# BC7.net
KiCad netlist of a schematic drawn in EAGLE
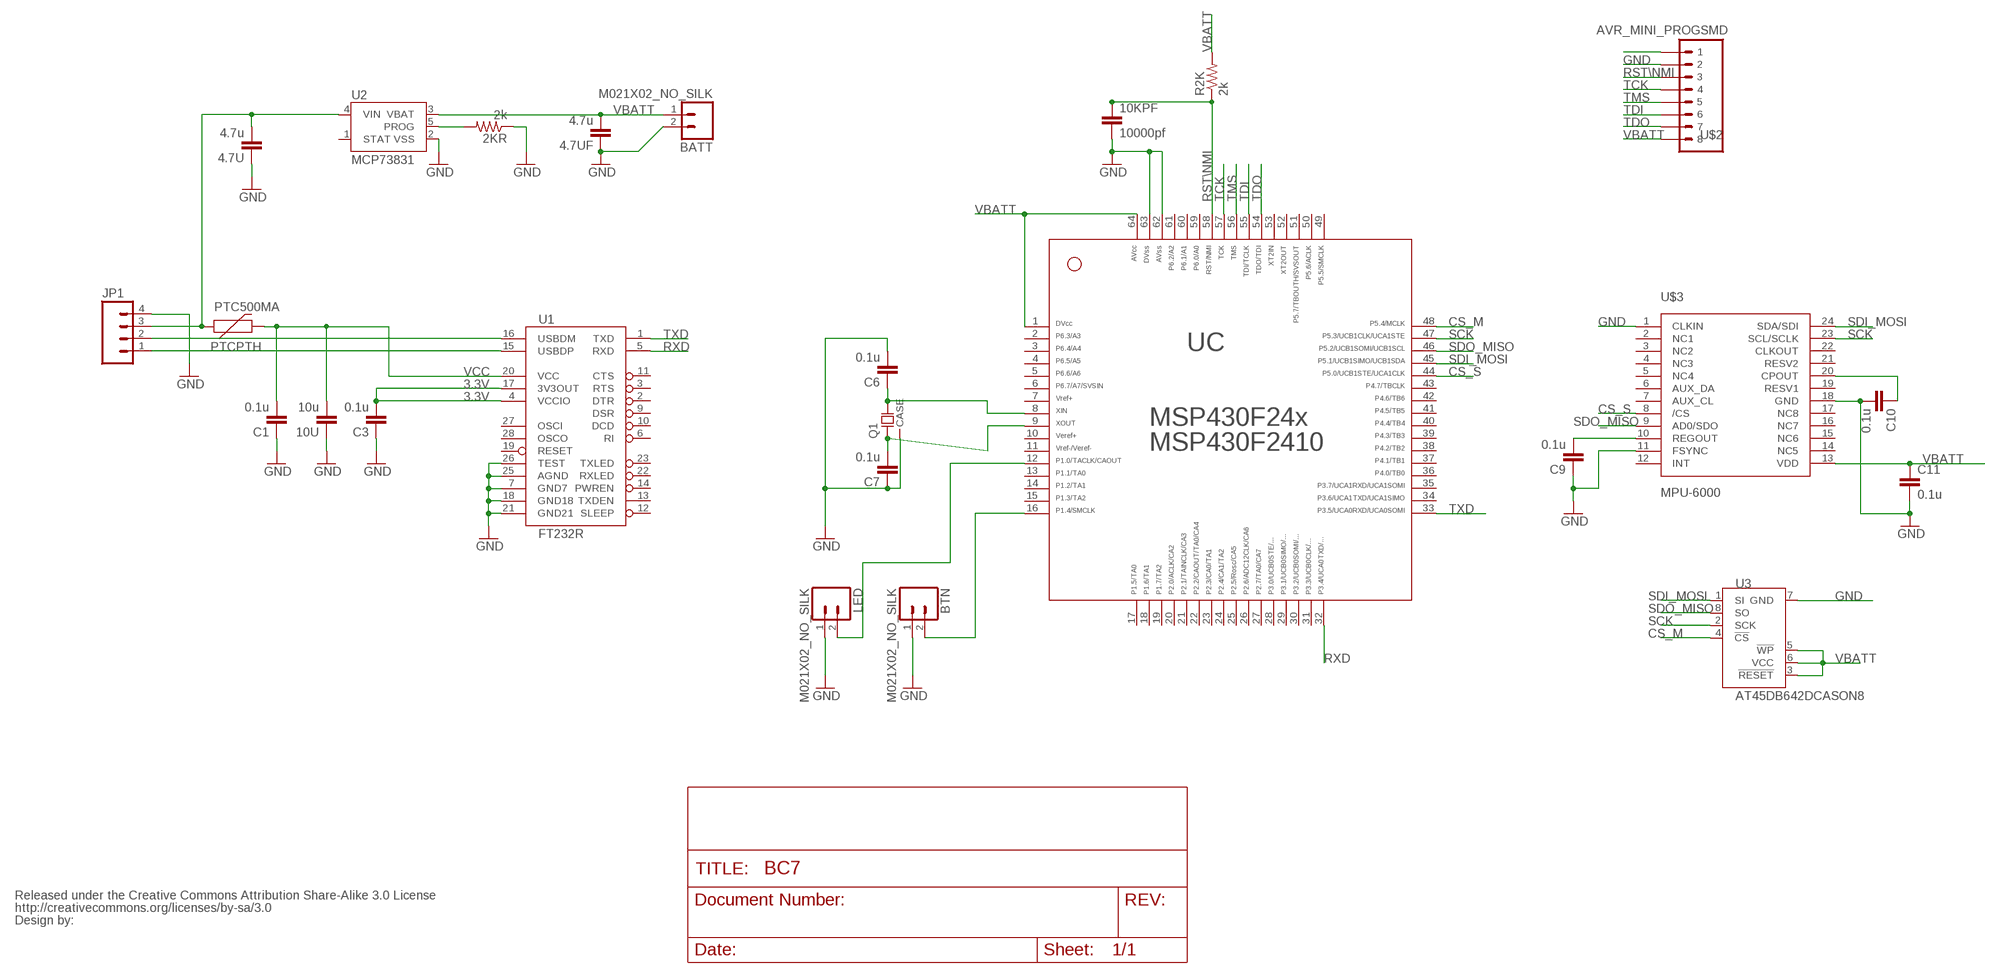
[diagram p0: schematic, sheet 1]

(export (version "E")
  (design (tool "Eeschema 10.0.6"))
  (components
    (comp (ref "2KR")
      (value "2k")
      (footprint "eagle-import:0402-RES")
      (libsource (lib "eagle-import") (part "RESISTOR0402-RES"))
    )
    (comp (ref "4.7U")
      (value "4.7u")
      (footprint "eagle-import:0402-CAP")
      (libsource (lib "eagle-import") (part "CAP0402-CAP"))
    )
    (comp (ref "4.7UF")
      (value "4.7u")
      (footprint "eagle-import:0402-CAP")
      (libsource (lib "eagle-import") (part "CAP0402-CAP"))
    )
    (comp (ref "10KPF")
      (value "10000pf")
      (footprint "eagle-import:CAP-PTH-SMALLEZ")
      (libsource (lib "eagle-import") (part "SparkFun-Passives_CAPEZ"))
    )
    (comp (ref "10U")
      (value "10u")
      (footprint "eagle-import:0402-CAP")
      (libsource (lib "eagle-import") (part "CAP0402-CAP"))
    )
    (comp (ref "BATT")
      (value "M021X02_NO_SILK")
      (footprint "eagle-import:1X02_NO_SILK")
      (libsource (lib "eagle-import") (part "M021X02_NO_SILK"))
    )
    (comp (ref "BTN")
      (value "M021X02_NO_SILK")
      (footprint "eagle-import:1X02_NO_SILK")
      (libsource (lib "eagle-import") (part "M021X02_NO_SILK"))
    )
    (comp (ref "C1")
      (value "0.1u")
      (footprint "eagle-import:0402-CAP")
      (libsource (lib "eagle-import") (part "CAP0402-CAP"))
    )
    (comp (ref "C3")
      (value "0.1u")
      (footprint "eagle-import:0402-CAP")
      (libsource (lib "eagle-import") (part "CAP0402-CAP"))
    )
    (comp (ref "C6")
      (value "0.1u")
      (footprint "eagle-import:0402-CAP")
      (libsource (lib "eagle-import") (part "CAP0402-CAP"))
    )
    (comp (ref "C7")
      (value "0.1u")
      (footprint "eagle-import:0402-CAP")
      (libsource (lib "eagle-import") (part "CAP0402-CAP"))
    )
    (comp (ref "C9")
      (value "0.1u")
      (footprint "eagle-import:0402-CAP")
      (libsource (lib "eagle-import") (part "CAP0402-CAP"))
    )
    (comp (ref "C10")
      (value "0.1u")
      (footprint "eagle-import:0402-CAP")
      (libsource (lib "eagle-import") (part "CAP0402-CAP"))
    )
    (comp (ref "C11")
      (value "0.1u")
      (footprint "eagle-import:0402-CAP")
      (libsource (lib "eagle-import") (part "CAP0402-CAP"))
    )
    (comp (ref "JP1")
      (value "M04LOCK")
      (footprint "eagle-import:1X04_LOCK")
      (libsource (lib "eagle-import") (part "M04LOCK"))
    )
    (comp (ref "LED")
      (value "M021X02_NO_SILK")
      (footprint "eagle-import:1X02_NO_SILK")
      (libsource (lib "eagle-import") (part "M021X02_NO_SILK"))
    )
    (comp (ref "PTC500MA")
      (value "PTCPTH")
      (footprint "eagle-import:PTC")
      (libsource (lib "eagle-import") (part "PTCPTH"))
    )
    (comp (ref "Q1")
      (value "MS1V-T1K-32.768KHZ/12.5PF/20PPM/TA/QC")
      (footprint "eagle-import:MS1V-T1K")
      (libsource (lib "eagle-import") (part "MS1V-T1K-32.768KHZ/12.5PF/20PPM/TA/QC"))
    )
    (comp (ref "R2K")
      (value "2k")
      (footprint "eagle-import:0204_5")
      (libsource (lib "eagle-import") (part "R-US_0204/5"))
    )
    (comp (ref "U$1")
      (value "CREATIVE_COMMONS")
      (footprint "eagle-import:CREATIVE_COMMONS")
      (libsource (lib "eagle-import") (part "CREATIVE_COMMONS"))
    )
    (comp (ref "U$2")
      (value "AVR_MINI_PROGSMD")
      (footprint "eagle-import:AVR_MINI_PROG")
      (libsource (lib "eagle-import") (part "AVR_MINI_PROGSMD"))
    )
    (comp (ref "U$3")
      (value "MPU-6000")
      (footprint "eagle-import:QFN-24")
      (libsource (lib "eagle-import") (part "MPU-6000"))
    )
    (comp (ref "U1")
      (value "FT232R")
      (footprint "eagle-import:SSOP28DB")
      (libsource (lib "eagle-import") (part "FT232RLSSOP"))
    )
    (comp (ref "U2")
      (value "MCP73831")
      (footprint "eagle-import:SOT23-5")
      (libsource (lib "eagle-import") (part "MCP73831"))
    )
    (comp (ref "U3")
      (value "AT45DB642DCASON8")
      (footprint "eagle-import:CASON8")
      (libsource (lib "eagle-import") (part "AT45DB642DCASON8"))
    )
    (comp (ref "UC")
      (value "F24[X/10]---PM64")
      (footprint "eagle-import:PM_PAG64")
      (libsource (lib "eagle-import") (part "F24[X/10]---PM64"))
    )
  )
  (nets
    (net (code "1") (name "/3.3V") (class "Default")
      (node (ref "C3") (pin "2") (pinfunction "2_2") (pintype "passive"))
      (node (ref "U1") (pin "17") (pinfunction "3V3OUT_17") (pintype "output"))
      (node (ref "U1") (pin "4") (pinfunction "VCCIO_4") (pintype "power_in"))
    )
    (net (code "2") (name "/CS_M") (class "Default")
      (node (ref "U3") (pin "4") (pinfunction "~{CS}_4") (pintype "input"))
      (node (ref "UC") (pin "48") (pinfunction "48_48") (pintype "bidirectional"))
    )
    (net (code "3") (name "/CS_S") (class "Default")
      (node (ref "U$3") (pin "8") (pinfunction "/CS_8") (pintype "bidirectional"))
      (node (ref "UC") (pin "44") (pinfunction "44_44") (pintype "bidirectional"))
    )
    (net (code "4") (name "/RST\\NMI") (class "Default")
      (node (ref "10KPF") (pin "1") (pinfunction "1_1") (pintype "passive"))
      (node (ref "R2K") (pin "1") (pinfunction "1_1") (pintype "passive"))
      (node (ref "U$2") (pin "3") (pinfunction "3_3") (pintype "passive"))
      (node (ref "UC") (pin "58") (pinfunction "58_58") (pintype "input"))
    )
    (net (code "5") (name "/RXD") (class "Default")
      (node (ref "U1") (pin "5") (pinfunction "RXD_5") (pintype "input"))
      (node (ref "UC") (pin "32") (pinfunction "32_32") (pintype "bidirectional"))
    )
    (net (code "6") (name "/SCK") (class "Default")
      (node (ref "U$3") (pin "23") (pinfunction "SCL/SCLK_23") (pintype "bidirectional"))
      (node (ref "U3") (pin "2") (pinfunction "SCK_2") (pintype "input"))
      (node (ref "UC") (pin "47") (pinfunction "47_47") (pintype "bidirectional"))
    )
    (net (code "7") (name "/SDI_MOSI") (class "Default")
      (node (ref "U$3") (pin "24") (pinfunction "SDA/SDI_24") (pintype "bidirectional"))
      (node (ref "U3") (pin "1") (pinfunction "SI_1") (pintype "input"))
      (node (ref "UC") (pin "45") (pinfunction "45_45") (pintype "bidirectional"))
    )
    (net (code "8") (name "/SDO_MISO") (class "Default")
      (node (ref "U$3") (pin "9") (pinfunction "AD0/SDO_9") (pintype "bidirectional"))
      (node (ref "U3") (pin "8") (pinfunction "SO_8") (pintype "output"))
      (node (ref "UC") (pin "46") (pinfunction "46_46") (pintype "bidirectional"))
    )
    (net (code "9") (name "/TCK") (class "Default")
      (node (ref "U$2") (pin "4") (pinfunction "4_4") (pintype "passive"))
      (node (ref "UC") (pin "57") (pinfunction "57_57") (pintype "input"))
    )
    (net (code "10") (name "/TDI") (class "Default")
      (node (ref "U$2") (pin "6") (pinfunction "6_6") (pintype "passive"))
      (node (ref "UC") (pin "55") (pinfunction "55_55") (pintype "input"))
    )
    (net (code "11") (name "/TDO") (class "Default")
      (node (ref "U$2") (pin "7") (pinfunction "7_7") (pintype "passive"))
      (node (ref "UC") (pin "54") (pinfunction "54_54") (pintype "bidirectional"))
    )
    (net (code "12") (name "/TMS") (class "Default")
      (node (ref "U$2") (pin "5") (pinfunction "5_5") (pintype "passive"))
      (node (ref "UC") (pin "56") (pinfunction "56_56") (pintype "input"))
    )
    (net (code "13") (name "/TXD") (class "Default")
      (node (ref "U1") (pin "1") (pinfunction "TXD_1") (pintype "output"))
      (node (ref "UC") (pin "33") (pinfunction "33_33") (pintype "bidirectional"))
    )
    (net (code "14") (name "/VBATT") (class "Default")
      (node (ref "4.7UF") (pin "2") (pinfunction "2_2") (pintype "passive"))
      (node (ref "BATT") (pin "1") (pinfunction "1_1") (pintype "passive"))
      (node (ref "C11") (pin "1") (pinfunction "1_1") (pintype "passive"))
      (node (ref "R2K") (pin "2") (pinfunction "2_2") (pintype "passive"))
      (node (ref "U$2") (pin "8") (pinfunction "8_8") (pintype "passive"))
      (node (ref "U$3") (pin "13") (pinfunction "VDD_13") (pintype "bidirectional"))
      (node (ref "U2") (pin "3") (pinfunction "VBAT_3") (pintype "power_in"))
      (node (ref "U3") (pin "3") (pinfunction "~{RESET}_3") (pintype "input"))
      (node (ref "U3") (pin "5") (pinfunction "~{WP}_5") (pintype "input"))
      (node (ref "U3") (pin "6") (pinfunction "VCC_6") (pintype "power_in"))
      (node (ref "UC") (pin "1") (pinfunction "1_1") (pintype "power_in"))
      (node (ref "UC") (pin "64") (pinfunction "64_64") (pintype "power_in"))
    )
    (net (code "15") (name "/VCC") (class "Default")
      (node (ref "10U") (pin "2") (pinfunction "2_2") (pintype "passive"))
      (node (ref "C1") (pin "2") (pinfunction "2_2") (pintype "passive"))
      (node (ref "PTC500MA") (pin "P$2") (pinfunction "2_P$2") (pintype "bidirectional"))
      (node (ref "U1") (pin "20") (pinfunction "VCC_20") (pintype "power_in"))
    )
    (net (code "16") (name "GND") (class "Default")
      (node (ref "10KPF") (pin "2") (pinfunction "2_2") (pintype "passive"))
      (node (ref "10U") (pin "1") (pinfunction "1_1") (pintype "passive"))
      (node (ref "2KR") (pin "1") (pinfunction "1_1") (pintype "passive"))
      (node (ref "4.7U") (pin "1") (pinfunction "1_1") (pintype "passive"))
      (node (ref "4.7UF") (pin "1") (pinfunction "1_1") (pintype "passive"))
      (node (ref "BATT") (pin "2") (pinfunction "2_2") (pintype "passive"))
      (node (ref "BTN") (pin "1") (pinfunction "1_1") (pintype "passive"))
      (node (ref "C1") (pin "1") (pinfunction "1_1") (pintype "passive"))
      (node (ref "C10") (pin "2") (pinfunction "2_2") (pintype "passive"))
      (node (ref "C11") (pin "2") (pinfunction "2_2") (pintype "passive"))
      (node (ref "C3") (pin "1") (pinfunction "1_1") (pintype "passive"))
      (node (ref "C6") (pin "2") (pinfunction "2_2") (pintype "passive"))
      (node (ref "C7") (pin "1") (pinfunction "1_1") (pintype "passive"))
      (node (ref "C9") (pin "1") (pinfunction "1_1") (pintype "passive"))
      (node (ref "JP1") (pin "4") (pinfunction "4_4") (pintype "passive"))
      (node (ref "LED") (pin "1") (pinfunction "1_1") (pintype "passive"))
      (node (ref "Q1") (pin "CASE") (pinfunction "CASE_CASE") (pintype "passive"))
      (node (ref "U$2") (pin "2") (pinfunction "2_2") (pintype "passive"))
      (node (ref "U$3") (pin "1") (pinfunction "CLKIN_1") (pintype "bidirectional"))
      (node (ref "U$3") (pin "11") (pinfunction "FSYNC_11") (pintype "bidirectional"))
      (node (ref "U$3") (pin "18") (pinfunction "GND_18") (pintype "bidirectional"))
      (node (ref "U1") (pin "18") (pinfunction "GND18_18") (pintype "power_in"))
      (node (ref "U1") (pin "21") (pinfunction "GND21_21") (pintype "power_in"))
      (node (ref "U1") (pin "25") (pinfunction "AGND_25") (pintype "power_in"))
      (node (ref "U1") (pin "26") (pinfunction "TEST_26") (pintype "input"))
      (node (ref "U1") (pin "7") (pinfunction "GND7_7") (pintype "power_in"))
      (node (ref "U2") (pin "2") (pinfunction "VSS_2") (pintype "power_in"))
      (node (ref "U3") (pin "7") (pinfunction "GND_7") (pintype "power_in"))
      (node (ref "UC") (pin "62") (pinfunction "62_62") (pintype "power_in"))
      (node (ref "UC") (pin "63") (pinfunction "63_63") (pintype "power_in"))
    )
    (net (code "17") (name "Net-(BTN-Pad2)") (class "Default")
      (node (ref "BTN") (pin "2") (pinfunction "2_2") (pintype "passive"))
      (node (ref "UC") (pin "16") (pinfunction "16_16") (pintype "bidirectional"))
    )
    (net (code "18") (name "Net-(C6-Pad1)") (class "Default")
      (node (ref "C6") (pin "1") (pinfunction "1_1") (pintype "passive"))
      (node (ref "Q1") (pin "2") (pinfunction "2_2") (pintype "passive"))
      (node (ref "UC") (pin "8") (pinfunction "8_8") (pintype "input"))
    )
    (net (code "19") (name "Net-(C7-Pad2)") (class "Default")
      (node (ref "C7") (pin "2") (pinfunction "2_2") (pintype "passive"))
      (node (ref "Q1") (pin "1") (pinfunction "1_1") (pintype "passive"))
      (node (ref "UC") (pin "9") (pinfunction "9_9") (pintype "output"))
    )
    (net (code "20") (name "Net-(LED-Pad2)") (class "Default")
      (node (ref "LED") (pin "2") (pinfunction "2_2") (pintype "passive"))
      (node (ref "UC") (pin "12") (pinfunction "12_12") (pintype "bidirectional"))
    )
    (net (code "21") (name "Net-(PTC500MA-1)") (class "Default")
      (node (ref "4.7U") (pin "2") (pinfunction "2_2") (pintype "passive"))
      (node (ref "JP1") (pin "3") (pinfunction "3_3") (pintype "passive"))
      (node (ref "PTC500MA") (pin "P$1") (pinfunction "1_P$1") (pintype "bidirectional"))
      (node (ref "U2") (pin "4") (pinfunction "VIN_4") (pintype "power_in"))
    )
    (net (code "22") (name "Net-(U$3-CPOUT)") (class "Default")
      (node (ref "C10") (pin "1") (pinfunction "1_1") (pintype "passive"))
      (node (ref "U$3") (pin "20") (pinfunction "CPOUT_20") (pintype "bidirectional"))
    )
    (net (code "23") (name "Net-(U$3-REGOUT)") (class "Default")
      (node (ref "C9") (pin "2") (pinfunction "2_2") (pintype "passive"))
      (node (ref "U$3") (pin "10") (pinfunction "REGOUT_10") (pintype "bidirectional"))
    )
    (net (code "24") (name "Net-(U1-USBDM)") (class "Default")
      (node (ref "JP1") (pin "2") (pinfunction "2_2") (pintype "passive"))
      (node (ref "U1") (pin "16") (pinfunction "USBDM_16") (pintype "bidirectional"))
    )
    (net (code "25") (name "Net-(U1-USBDP)") (class "Default")
      (node (ref "JP1") (pin "1") (pinfunction "1_1") (pintype "passive"))
      (node (ref "U1") (pin "15") (pinfunction "USBDP_15") (pintype "bidirectional"))
    )
    (net (code "26") (name "Net-(U2-PROG)") (class "Default")
      (node (ref "2KR") (pin "2") (pinfunction "2_2") (pintype "passive"))
      (node (ref "U2") (pin "5") (pinfunction "PROG_5") (pintype "input"))
    )
    (net (code "27") (name "unconnected-(U$2-Pad1)") (class "Default")
      (node (ref "U$2") (pin "1") (pinfunction "1_1") (pintype "passive"))
    )
    (net (code "28") (name "unconnected-(U$3-AUX_CL-Pad7)") (class "Default")
      (node (ref "U$3") (pin "7") (pinfunction "AUX_CL_7") (pintype "bidirectional"))
    )
    (net (code "29") (name "unconnected-(U$3-AUX_DA-Pad6)") (class "Default")
      (node (ref "U$3") (pin "6") (pinfunction "AUX_DA_6") (pintype "bidirectional"))
    )
    (net (code "30") (name "unconnected-(U$3-CLKOUT-Pad22)") (class "Default")
      (node (ref "U$3") (pin "22") (pinfunction "CLKOUT_22") (pintype "bidirectional"))
    )
    (net (code "31") (name "unconnected-(U$3-INT-Pad12)") (class "Default")
      (node (ref "U$3") (pin "12") (pinfunction "INT_12") (pintype "bidirectional"))
    )
    (net (code "32") (name "unconnected-(U$3-NC1-Pad2)") (class "Default")
      (node (ref "U$3") (pin "2") (pinfunction "NC1_2") (pintype "bidirectional"))
    )
    (net (code "33") (name "unconnected-(U$3-NC2-Pad3)") (class "Default")
      (node (ref "U$3") (pin "3") (pinfunction "NC2_3") (pintype "bidirectional"))
    )
    (net (code "34") (name "unconnected-(U$3-NC3-Pad4)") (class "Default")
      (node (ref "U$3") (pin "4") (pinfunction "NC3_4") (pintype "bidirectional"))
    )
    (net (code "35") (name "unconnected-(U$3-NC4-Pad5)") (class "Default")
      (node (ref "U$3") (pin "5") (pinfunction "NC4_5") (pintype "bidirectional"))
    )
    (net (code "36") (name "unconnected-(U$3-NC5-Pad14)") (class "Default")
      (node (ref "U$3") (pin "14") (pinfunction "NC5_14") (pintype "bidirectional"))
    )
    (net (code "37") (name "unconnected-(U$3-NC6-Pad15)") (class "Default")
      (node (ref "U$3") (pin "15") (pinfunction "NC6_15") (pintype "bidirectional"))
    )
    (net (code "38") (name "unconnected-(U$3-NC7-Pad16)") (class "Default")
      (node (ref "U$3") (pin "16") (pinfunction "NC7_16") (pintype "bidirectional"))
    )
    (net (code "39") (name "unconnected-(U$3-NC8-Pad17)") (class "Default")
      (node (ref "U$3") (pin "17") (pinfunction "NC8_17") (pintype "bidirectional"))
    )
    (net (code "40") (name "unconnected-(U$3-RESV1-Pad19)") (class "Default")
      (node (ref "U$3") (pin "19") (pinfunction "RESV1_19") (pintype "bidirectional"))
    )
    (net (code "41") (name "unconnected-(U$3-RESV2-Pad21)") (class "Default")
      (node (ref "U$3") (pin "21") (pinfunction "RESV2_21") (pintype "bidirectional"))
    )
    (net (code "42") (name "unconnected-(U1-CTS-Pad11)") (class "Default")
      (node (ref "U1") (pin "11") (pinfunction "CTS_11") (pintype "input"))
    )
    (net (code "43") (name "unconnected-(U1-DCD-Pad10)") (class "Default")
      (node (ref "U1") (pin "10") (pinfunction "DCD_10") (pintype "input"))
    )
    (net (code "44") (name "unconnected-(U1-DSR-Pad9)") (class "Default")
      (node (ref "U1") (pin "9") (pinfunction "DSR_9") (pintype "input"))
    )
    (net (code "45") (name "unconnected-(U1-DTR-Pad2)") (class "Default")
      (node (ref "U1") (pin "2") (pinfunction "DTR_2") (pintype "output"))
    )
    (net (code "46") (name "unconnected-(U1-OSCI-Pad27)") (class "Default")
      (node (ref "U1") (pin "27") (pinfunction "OSCI_27") (pintype "input"))
    )
    (net (code "47") (name "unconnected-(U1-OSCO-Pad28)") (class "Default")
      (node (ref "U1") (pin "28") (pinfunction "OSCO_28") (pintype "output"))
    )
    (net (code "48") (name "unconnected-(U1-PWREN-Pad14)") (class "Default")
      (node (ref "U1") (pin "14") (pinfunction "PWREN_14") (pintype "input"))
    )
    (net (code "49") (name "unconnected-(U1-RESET-Pad19)") (class "Default")
      (node (ref "U1") (pin "19") (pinfunction "RESET_19") (pintype "input"))
    )
    (net (code "50") (name "unconnected-(U1-RI-Pad6)") (class "Default")
      (node (ref "U1") (pin "6") (pinfunction "RI_6") (pintype "input"))
    )
    (net (code "51") (name "unconnected-(U1-RTS-Pad3)") (class "Default")
      (node (ref "U1") (pin "3") (pinfunction "RTS_3") (pintype "output"))
    )
    (net (code "52") (name "unconnected-(U1-RXLED-Pad22)") (class "Default")
      (node (ref "U1") (pin "22") (pinfunction "RXLED_22") (pintype "input"))
    )
    (net (code "53") (name "unconnected-(U1-SLEEP-Pad12)") (class "Default")
      (node (ref "U1") (pin "12") (pinfunction "SLEEP_12") (pintype "input"))
    )
    (net (code "54") (name "unconnected-(U1-TXDEN-Pad13)") (class "Default")
      (node (ref "U1") (pin "13") (pinfunction "TXDEN_13") (pintype "input"))
    )
    (net (code "55") (name "unconnected-(U1-TXLED-Pad23)") (class "Default")
      (node (ref "U1") (pin "23") (pinfunction "TXLED_23") (pintype "input"))
    )
    (net (code "56") (name "unconnected-(U2-STAT-Pad1)") (class "Default")
      (node (ref "U2") (pin "1") (pinfunction "STAT_1") (pintype "output"))
    )
    (net (code "57") (name "unconnected-(UC-Pad2)") (class "Default")
      (node (ref "UC") (pin "2") (pinfunction "2_2") (pintype "bidirectional"))
    )
    (net (code "58") (name "unconnected-(UC-Pad3)") (class "Default")
      (node (ref "UC") (pin "3") (pinfunction "3_3") (pintype "bidirectional"))
    )
    (net (code "59") (name "unconnected-(UC-Pad4)") (class "Default")
      (node (ref "UC") (pin "4") (pinfunction "4_4") (pintype "bidirectional"))
    )
    (net (code "60") (name "unconnected-(UC-Pad5)") (class "Default")
      (node (ref "UC") (pin "5") (pinfunction "5_5") (pintype "bidirectional"))
    )
    (net (code "61") (name "unconnected-(UC-Pad6)") (class "Default")
      (node (ref "UC") (pin "6") (pinfunction "6_6") (pintype "bidirectional"))
    )
    (net (code "62") (name "unconnected-(UC-Pad7)") (class "Default")
      (node (ref "UC") (pin "7") (pinfunction "7_7") (pintype "output"))
    )
    (net (code "63") (name "unconnected-(UC-Pad10)") (class "Default")
      (node (ref "UC") (pin "10") (pinfunction "10_10") (pintype "output"))
    )
    (net (code "64") (name "unconnected-(UC-Pad11)") (class "Default")
      (node (ref "UC") (pin "11") (pinfunction "11_11") (pintype "input"))
    )
    (net (code "65") (name "unconnected-(UC-Pad13)") (class "Default")
      (node (ref "UC") (pin "13") (pinfunction "13_13") (pintype "bidirectional"))
    )
    (net (code "66") (name "unconnected-(UC-Pad14)") (class "Default")
      (node (ref "UC") (pin "14") (pinfunction "14_14") (pintype "bidirectional"))
    )
    (net (code "67") (name "unconnected-(UC-Pad15)") (class "Default")
      (node (ref "UC") (pin "15") (pinfunction "15_15") (pintype "bidirectional"))
    )
    (net (code "68") (name "unconnected-(UC-Pad17)") (class "Default")
      (node (ref "UC") (pin "17") (pinfunction "17_17") (pintype "bidirectional"))
    )
    (net (code "69") (name "unconnected-(UC-Pad18)") (class "Default")
      (node (ref "UC") (pin "18") (pinfunction "18_18") (pintype "bidirectional"))
    )
    (net (code "70") (name "unconnected-(UC-Pad19)") (class "Default")
      (node (ref "UC") (pin "19") (pinfunction "19_19") (pintype "bidirectional"))
    )
    (net (code "71") (name "unconnected-(UC-Pad20)") (class "Default")
      (node (ref "UC") (pin "20") (pinfunction "20_20") (pintype "bidirectional"))
    )
    (net (code "72") (name "unconnected-(UC-Pad21)") (class "Default")
      (node (ref "UC") (pin "21") (pinfunction "21_21") (pintype "bidirectional"))
    )
    (net (code "73") (name "unconnected-(UC-Pad22)") (class "Default")
      (node (ref "UC") (pin "22") (pinfunction "22_22") (pintype "bidirectional"))
    )
    (net (code "74") (name "unconnected-(UC-Pad23)") (class "Default")
      (node (ref "UC") (pin "23") (pinfunction "23_23") (pintype "bidirectional"))
    )
    (net (code "75") (name "unconnected-(UC-Pad24)") (class "Default")
      (node (ref "UC") (pin "24") (pinfunction "24_24") (pintype "bidirectional"))
    )
    (net (code "76") (name "unconnected-(UC-Pad25)") (class "Default")
      (node (ref "UC") (pin "25") (pinfunction "25_25") (pintype "bidirectional"))
    )
    (net (code "77") (name "unconnected-(UC-Pad26)") (class "Default")
      (node (ref "UC") (pin "26") (pinfunction "26_26") (pintype "bidirectional"))
    )
    (net (code "78") (name "unconnected-(UC-Pad27)") (class "Default")
      (node (ref "UC") (pin "27") (pinfunction "27_27") (pintype "bidirectional"))
    )
    (net (code "79") (name "unconnected-(UC-Pad28)") (class "Default")
      (node (ref "UC") (pin "28") (pinfunction "28_28") (pintype "bidirectional"))
    )
    (net (code "80") (name "unconnected-(UC-Pad29)") (class "Default")
      (node (ref "UC") (pin "29") (pinfunction "29_29") (pintype "bidirectional"))
    )
    (net (code "81") (name "unconnected-(UC-Pad30)") (class "Default")
      (node (ref "UC") (pin "30") (pinfunction "30_30") (pintype "bidirectional"))
    )
    (net (code "82") (name "unconnected-(UC-Pad31)") (class "Default")
      (node (ref "UC") (pin "31") (pinfunction "31_31") (pintype "bidirectional"))
    )
    (net (code "83") (name "unconnected-(UC-Pad34)") (class "Default")
      (node (ref "UC") (pin "34") (pinfunction "34_34") (pintype "bidirectional"))
    )
    (net (code "84") (name "unconnected-(UC-Pad35)") (class "Default")
      (node (ref "UC") (pin "35") (pinfunction "35_35") (pintype "bidirectional"))
    )
    (net (code "85") (name "unconnected-(UC-Pad36)") (class "Default")
      (node (ref "UC") (pin "36") (pinfunction "36_36") (pintype "bidirectional"))
    )
    (net (code "86") (name "unconnected-(UC-Pad37)") (class "Default")
      (node (ref "UC") (pin "37") (pinfunction "37_37") (pintype "bidirectional"))
    )
    (net (code "87") (name "unconnected-(UC-Pad38)") (class "Default")
      (node (ref "UC") (pin "38") (pinfunction "38_38") (pintype "bidirectional"))
    )
    (net (code "88") (name "unconnected-(UC-Pad39)") (class "Default")
      (node (ref "UC") (pin "39") (pinfunction "39_39") (pintype "bidirectional"))
    )
    (net (code "89") (name "unconnected-(UC-Pad40)") (class "Default")
      (node (ref "UC") (pin "40") (pinfunction "40_40") (pintype "bidirectional"))
    )
    (net (code "90") (name "unconnected-(UC-Pad41)") (class "Default")
      (node (ref "UC") (pin "41") (pinfunction "41_41") (pintype "bidirectional"))
    )
    (net (code "91") (name "unconnected-(UC-Pad42)") (class "Default")
      (node (ref "UC") (pin "42") (pinfunction "42_42") (pintype "bidirectional"))
    )
    (net (code "92") (name "unconnected-(UC-Pad43)") (class "Default")
      (node (ref "UC") (pin "43") (pinfunction "43_43") (pintype "bidirectional"))
    )
    (net (code "93") (name "unconnected-(UC-Pad49)") (class "Default")
      (node (ref "UC") (pin "49") (pinfunction "49_49") (pintype "bidirectional"))
    )
    (net (code "94") (name "unconnected-(UC-Pad50)") (class "Default")
      (node (ref "UC") (pin "50") (pinfunction "50_50") (pintype "bidirectional"))
    )
    (net (code "95") (name "unconnected-(UC-Pad51)") (class "Default")
      (node (ref "UC") (pin "51") (pinfunction "51_51") (pintype "bidirectional"))
    )
    (net (code "96") (name "unconnected-(UC-Pad52)") (class "Default")
      (node (ref "UC") (pin "52") (pinfunction "52_52") (pintype "output"))
    )
    (net (code "97") (name "unconnected-(UC-Pad53)") (class "Default")
      (node (ref "UC") (pin "53") (pinfunction "53_53") (pintype "input"))
    )
    (net (code "98") (name "unconnected-(UC-Pad59)") (class "Default")
      (node (ref "UC") (pin "59") (pinfunction "59_59") (pintype "bidirectional"))
    )
    (net (code "99") (name "unconnected-(UC-Pad60)") (class "Default")
      (node (ref "UC") (pin "60") (pinfunction "60_60") (pintype "bidirectional"))
    )
    (net (code "100") (name "unconnected-(UC-Pad61)") (class "Default")
      (node (ref "UC") (pin "61") (pinfunction "61_61") (pintype "bidirectional"))
    )
  )
)
